# SCH_orange_pi_zero_2022-04-15.net
KiCad netlist of a schematic drawn in EasyEDA
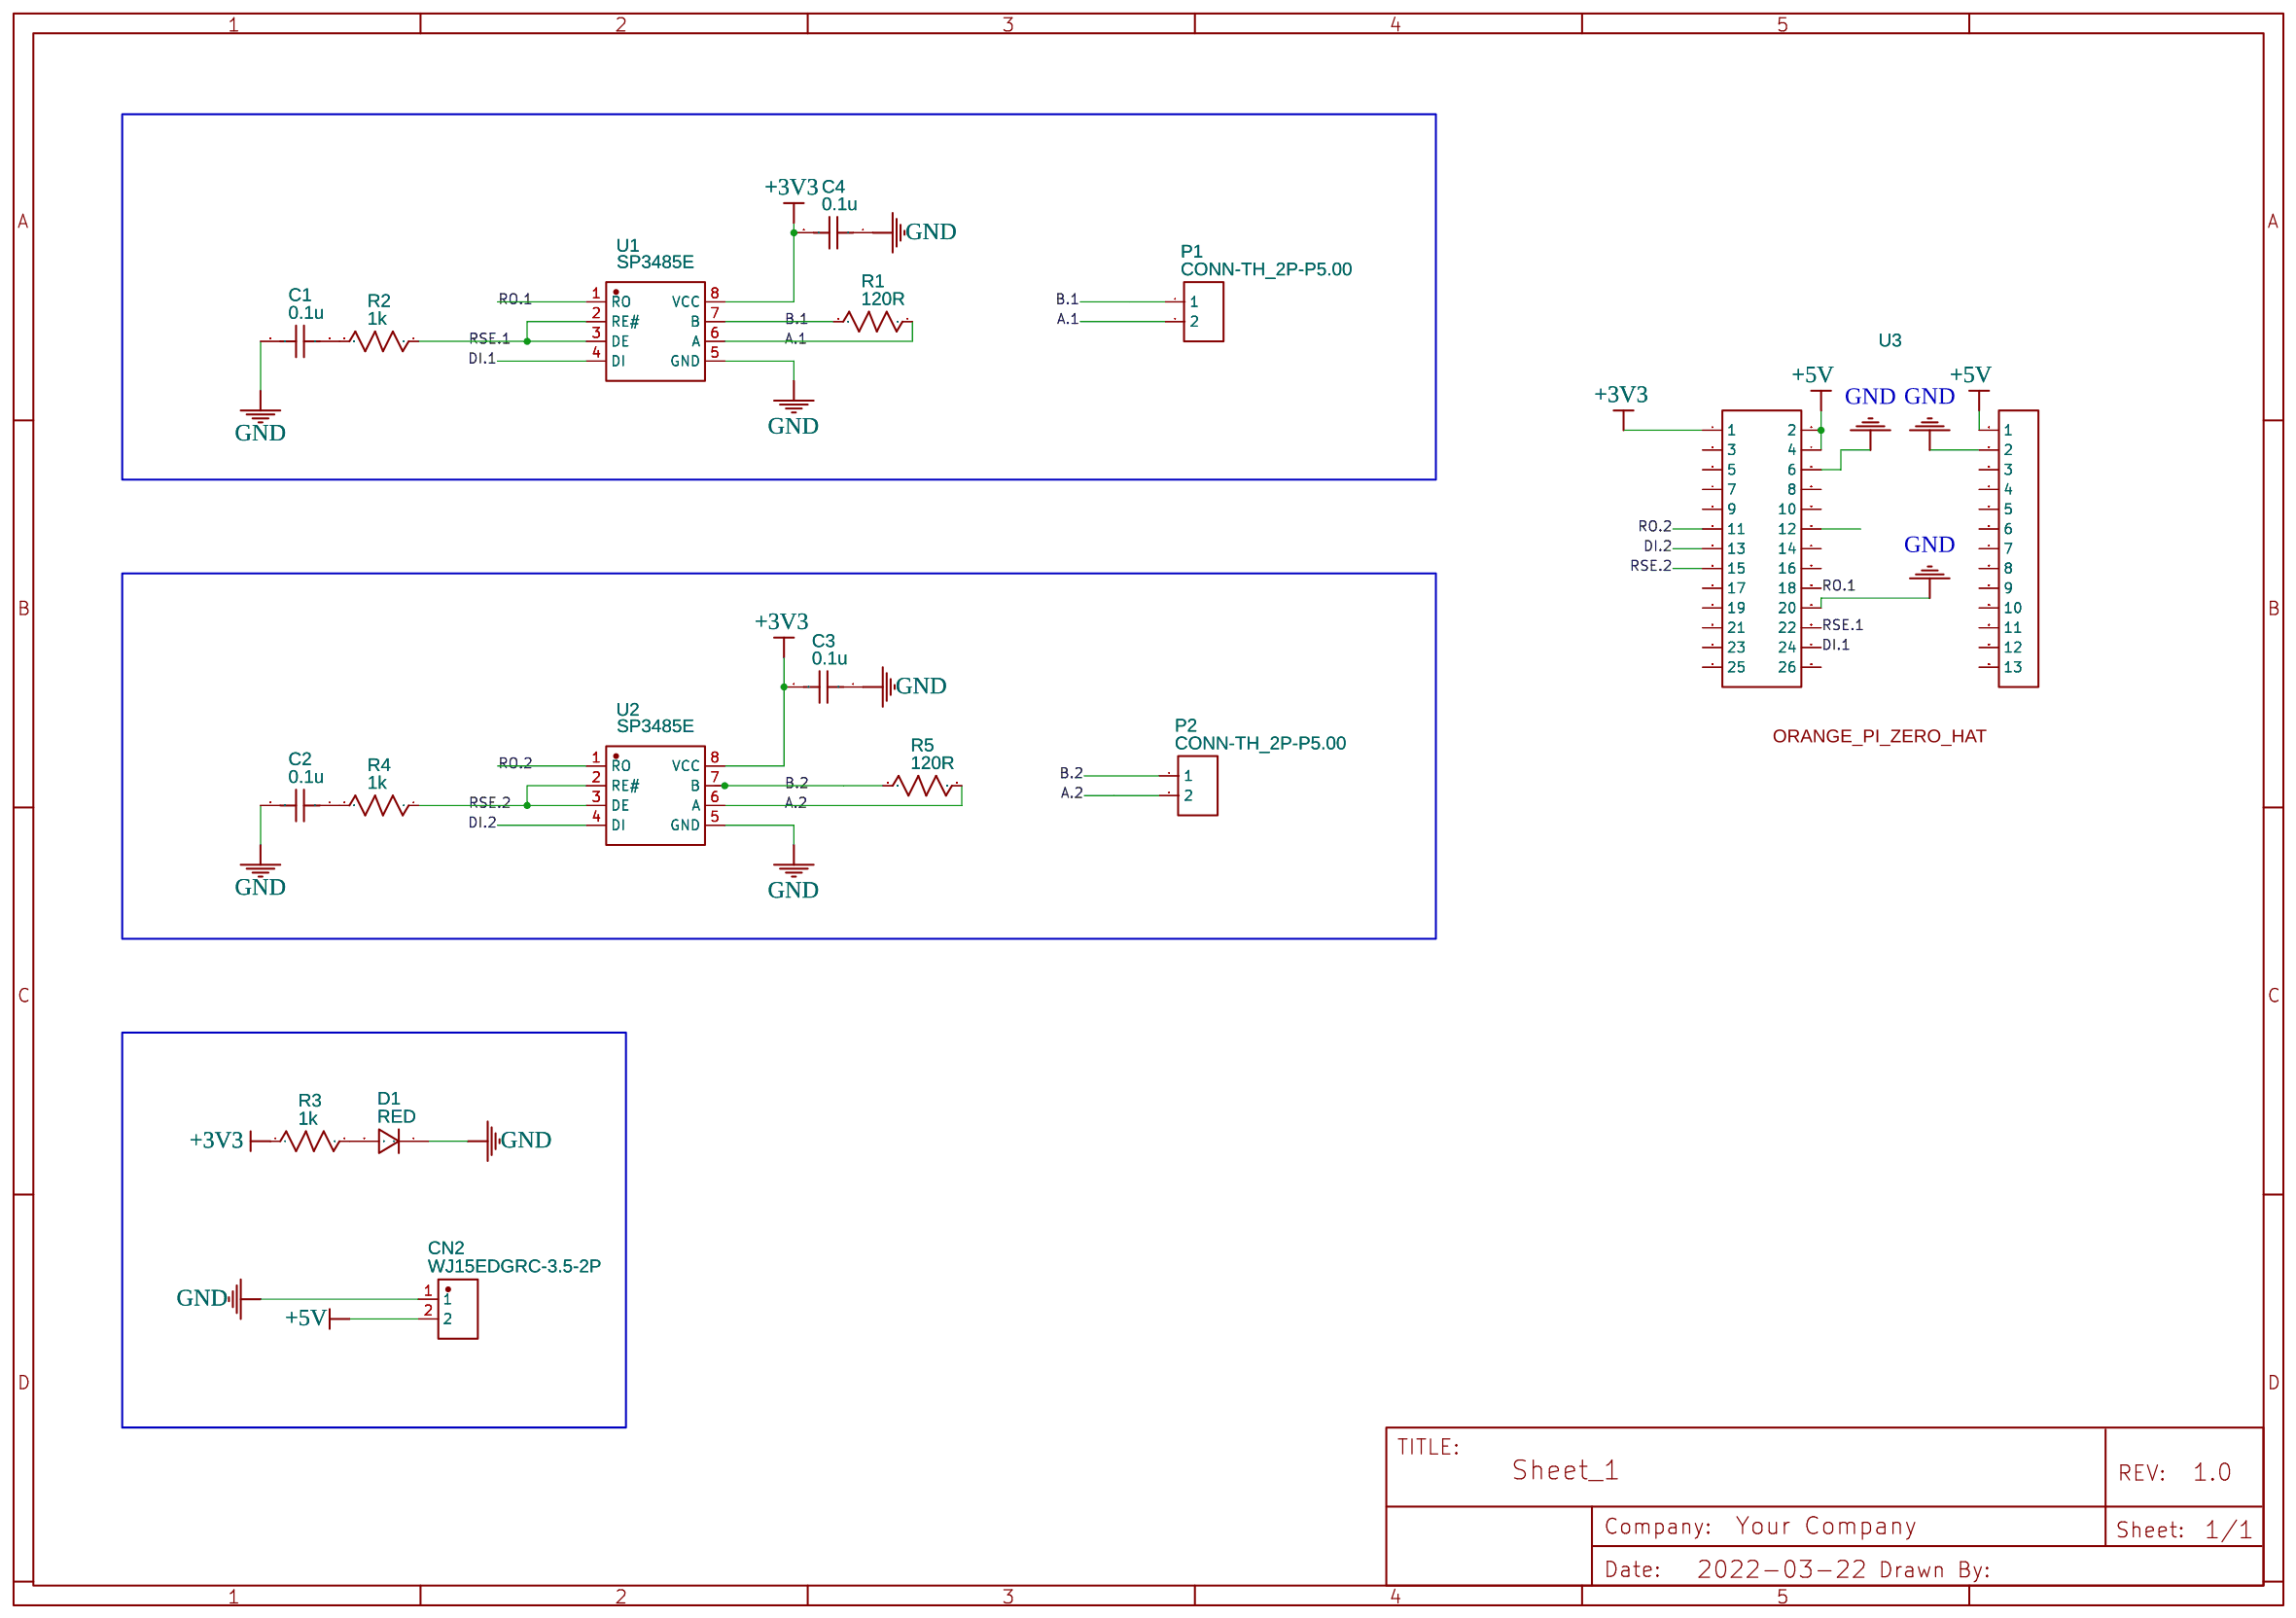
[diagram p0: schematic sheet]

(export (version "E")
  (design (tool "Eeschema 10.0.6"))
  (components
    (comp (ref "C1") (value "0.1u") (libsource (lib "") (part "C_0603_US")))
    (comp (ref "C2") (value "0.1u") (libsource (lib "") (part "C_0603_US")))
    (comp (ref "C3") (value "0.1u") (libsource (lib "") (part "C_0603_US")))
    (comp (ref "C4") (value "0.1u") (libsource (lib "") (part "C_0603_US")))
    (comp (ref "CN2")
      (value "WJ15EDGRC-3.5-2P")
      (fields (field (name "BOM_Supplier Part") "C2924837"))
      (libsource (lib "") (part "WJ15EDGRC-3.5-2P"))
    )
    (comp (ref "D1")
      (value "RED")
      (fields (field (name "BOM_Manufacturer Part") "1N4007W") (field (name "BOM_Supplier Part") "C328592"))
      (libsource (lib "") (part "1N4007W"))
    )
    (comp (ref "P1") (value "CONN-TH_2P-P5.00") (libsource (lib "") (part "CONN-TH_2P-P5.00")))
    (comp (ref "P2") (value "CONN-TH_2P-P5.00") (libsource (lib "") (part "CONN-TH_2P-P5.00")))
    (comp (ref "R1") (value "120R") (libsource (lib "") (part "R_0603_US")))
    (comp (ref "R2") (value "1k") (libsource (lib "") (part "R_0603_US")))
    (comp (ref "R3") (value "1k") (libsource (lib "") (part "R_0603_US_1")))
    (comp (ref "R4") (value "1k") (libsource (lib "") (part "R_0603_US")))
    (comp (ref "R5") (value "120R") (libsource (lib "") (part "R_0603_US")))
    (comp (ref "U1")
      (value "SP3485E")
      (fields
        (field (name "BOM_Manufacturer Part") "SP3485EN-L/TR")
        (field (name "BOM_Supplier Part") "C8963")
      )
      (libsource (lib "") (part "SP3485EN-L/TR"))
    )
    (comp (ref "U2")
      (value "SP3485E")
      (fields
        (field (name "BOM_Manufacturer Part") "SP3485EN-L/TR")
        (field (name "BOM_Supplier Part") "C8963")
      )
      (libsource (lib "") (part "SP3485EN-L/TR"))
    )
    (comp (ref "U3") (value "HDR-F-2.54_2x13") (libsource (lib "") (part "HDR-F-2.54_2x13")))
  )
  (nets
    (net (code "1") (name "+3V3") (class "Default")
      (node (ref "C3") (pin "2") (pinfunction "2_2") (pintype "unspecified"))
      (node (ref "C4") (pin "2") (pinfunction "2_2") (pintype "unspecified"))
      (node (ref "R3") (pin "1") (pinfunction "1_1") (pintype "unspecified"))
      (node (ref "U1") (pin "8") (pinfunction "VCC_8") (pintype "unspecified"))
      (node (ref "U2") (pin "8") (pinfunction "VCC_8") (pintype "unspecified"))
      (node (ref "U3") (pin "1") (pinfunction "1_1") (pintype "passive"))
    )
    (net (code "2") (name "+5V") (class "Default")
      (node (ref "CN2") (pin "2") (pinfunction "2_2") (pintype "unspecified"))
      (node (ref "U3") (pin "2") (pinfunction "2_2") (pintype "passive"))
      (node (ref "U3") (pin "4") (pinfunction "4_4") (pintype "passive"))
      (node (ref "U3") (pin "e1") (pinfunction "1_e1") (pintype "unspecified"))
    )
    (net (code "3") (name "/A.1") (class "Default")
      (node (ref "P1") (pin "2") (pinfunction "2_2") (pintype "unspecified"))
      (node (ref "R1") (pin "1") (pinfunction "1_1") (pintype "unspecified"))
      (node (ref "U1") (pin "6") (pinfunction "A_6") (pintype "unspecified"))
    )
    (net (code "4") (name "/A.2") (class "Default")
      (node (ref "P2") (pin "2") (pinfunction "2_2") (pintype "unspecified"))
      (node (ref "R5") (pin "1") (pinfunction "1_1") (pintype "unspecified"))
      (node (ref "U2") (pin "6") (pinfunction "A_6") (pintype "unspecified"))
    )
    (net (code "5") (name "/B.1") (class "Default")
      (node (ref "P1") (pin "1") (pinfunction "1_1") (pintype "unspecified"))
      (node (ref "R1") (pin "2") (pinfunction "2_2") (pintype "unspecified"))
      (node (ref "U1") (pin "7") (pinfunction "B_7") (pintype "unspecified"))
    )
    (net (code "6") (name "/B.2") (class "Default")
      (node (ref "P2") (pin "1") (pinfunction "1_1") (pintype "unspecified"))
      (node (ref "R5") (pin "2") (pinfunction "2_2") (pintype "unspecified"))
      (node (ref "U2") (pin "7") (pinfunction "B_7") (pintype "unspecified"))
    )
    (net (code "7") (name "/DI.1") (class "Default")
      (node (ref "U1") (pin "4") (pinfunction "DI_4") (pintype "unspecified"))
      (node (ref "U3") (pin "24") (pinfunction "24_24") (pintype "input"))
    )
    (net (code "8") (name "/DI.2") (class "Default")
      (node (ref "U2") (pin "4") (pinfunction "DI_4") (pintype "unspecified"))
      (node (ref "U3") (pin "13") (pinfunction "13_13") (pintype "input"))
    )
    (net (code "9") (name "/RO.1") (class "Default")
      (node (ref "U1") (pin "1") (pinfunction "RO_1") (pintype "unspecified"))
      (node (ref "U3") (pin "18") (pinfunction "18_18") (pintype "input"))
    )
    (net (code "10") (name "/RO.2") (class "Default")
      (node (ref "U2") (pin "1") (pinfunction "RO_1") (pintype "unspecified"))
      (node (ref "U3") (pin "11") (pinfunction "11_11") (pintype "input"))
    )
    (net (code "11") (name "/RSE.1") (class "Default")
      (node (ref "R2") (pin "1") (pinfunction "1_1") (pintype "unspecified"))
      (node (ref "U1") (pin "2") (pinfunction "RE#_2") (pintype "unspecified"))
      (node (ref "U1") (pin "3") (pinfunction "DE_3") (pintype "unspecified"))
      (node (ref "U3") (pin "22") (pinfunction "22_22") (pintype "input"))
    )
    (net (code "12") (name "/RSE.2") (class "Default")
      (node (ref "R4") (pin "1") (pinfunction "1_1") (pintype "unspecified"))
      (node (ref "U2") (pin "2") (pinfunction "RE#_2") (pintype "unspecified"))
      (node (ref "U2") (pin "3") (pinfunction "DE_3") (pintype "unspecified"))
      (node (ref "U3") (pin "15") (pinfunction "15_15") (pintype "input"))
    )
    (net (code "13") (name "GND") (class "Default")
      (node (ref "C1") (pin "2") (pinfunction "2_2") (pintype "unspecified"))
      (node (ref "C2") (pin "2") (pinfunction "2_2") (pintype "unspecified"))
      (node (ref "C3") (pin "1") (pinfunction "1_1") (pintype "unspecified"))
      (node (ref "C4") (pin "1") (pinfunction "1_1") (pintype "unspecified"))
      (node (ref "CN2") (pin "1") (pinfunction "1_1") (pintype "unspecified"))
      (node (ref "D1") (pin "1") (pinfunction "1_1") (pintype "unspecified"))
      (node (ref "U1") (pin "5") (pinfunction "GND_5") (pintype "unspecified"))
      (node (ref "U2") (pin "5") (pinfunction "GND_5") (pintype "unspecified"))
      (node (ref "U3") (pin "20") (pinfunction "20_20") (pintype "input"))
      (node (ref "U3") (pin "6") (pinfunction "6_6") (pintype "input"))
      (node (ref "U3") (pin "e2") (pinfunction "2_e2") (pintype "unspecified"))
    )
    (net (code "14") (name "Net-(C1-Pad1)") (class "Default")
      (node (ref "C1") (pin "1") (pinfunction "1_1") (pintype "unspecified"))
      (node (ref "R2") (pin "2") (pinfunction "2_2") (pintype "unspecified"))
    )
    (net (code "15") (name "Net-(C2-Pad1)") (class "Default")
      (node (ref "C2") (pin "1") (pinfunction "1_1") (pintype "unspecified"))
      (node (ref "R4") (pin "2") (pinfunction "2_2") (pintype "unspecified"))
    )
    (net (code "16") (name "Net-(D1-Pad2)") (class "Default")
      (node (ref "D1") (pin "2") (pinfunction "2_2") (pintype "unspecified"))
      (node (ref "R3") (pin "2") (pinfunction "2_2") (pintype "unspecified"))
    )
    (net (code "17") (name "unconnected-(U3-3-Pade3)") (class "Default")
      (node (ref "U3") (pin "e3") (pinfunction "3_e3") (pintype "unspecified"))
    )
    (net (code "18") (name "unconnected-(U3-4-Pade4)") (class "Default")
      (node (ref "U3") (pin "e4") (pinfunction "4_e4") (pintype "unspecified"))
    )
    (net (code "19") (name "unconnected-(U3-5-Pade5)") (class "Default")
      (node (ref "U3") (pin "e5") (pinfunction "5_e5") (pintype "unspecified"))
    )
    (net (code "20") (name "unconnected-(U3-6-Pade6)") (class "Default")
      (node (ref "U3") (pin "e6") (pinfunction "6_e6") (pintype "unspecified"))
    )
    (net (code "21") (name "unconnected-(U3-7-Pade7)") (class "Default")
      (node (ref "U3") (pin "e7") (pinfunction "7_e7") (pintype "unspecified"))
    )
    (net (code "22") (name "unconnected-(U3-8-Pade8)") (class "Default")
      (node (ref "U3") (pin "e8") (pinfunction "8_e8") (pintype "unspecified"))
    )
    (net (code "23") (name "unconnected-(U3-9-Pade9)") (class "Default")
      (node (ref "U3") (pin "e9") (pinfunction "9_e9") (pintype "unspecified"))
    )
    (net (code "24") (name "unconnected-(U3-10-Pade10)") (class "Default")
      (node (ref "U3") (pin "e10") (pinfunction "10_e10") (pintype "unspecified"))
    )
    (net (code "25") (name "unconnected-(U3-11-Pade11)") (class "Default")
      (node (ref "U3") (pin "e11") (pinfunction "11_e11") (pintype "unspecified"))
    )
    (net (code "26") (name "unconnected-(U3-12-Pade12)") (class "Default")
      (node (ref "U3") (pin "e12") (pinfunction "12_e12") (pintype "unspecified"))
    )
    (net (code "27") (name "unconnected-(U3-13-Pade13)") (class "Default")
      (node (ref "U3") (pin "e13") (pinfunction "13_e13") (pintype "unspecified"))
    )
    (net (code "28") (name "unconnected-(U3-Pad3)") (class "Default")
      (node (ref "U3") (pin "3") (pinfunction "3_3") (pintype "input"))
    )
    (net (code "29") (name "unconnected-(U3-Pad5)") (class "Default")
      (node (ref "U3") (pin "5") (pinfunction "5_5") (pintype "input"))
    )
    (net (code "30") (name "unconnected-(U3-Pad7)") (class "Default")
      (node (ref "U3") (pin "7") (pinfunction "7_7") (pintype "input"))
    )
    (net (code "31") (name "unconnected-(U3-Pad8)") (class "Default")
      (node (ref "U3") (pin "8") (pinfunction "8_8") (pintype "input"))
    )
    (net (code "32") (name "unconnected-(U3-Pad9)") (class "Default")
      (node (ref "U3") (pin "9") (pinfunction "9_9") (pintype "input"))
    )
    (net (code "33") (name "unconnected-(U3-Pad10)") (class "Default")
      (node (ref "U3") (pin "10") (pinfunction "10_10") (pintype "input"))
    )
    (net (code "34") (name "unconnected-(U3-Pad12)") (class "Default")
      (node (ref "U3") (pin "12") (pinfunction "12_12") (pintype "input"))
    )
    (net (code "35") (name "unconnected-(U3-Pad14)") (class "Default")
      (node (ref "U3") (pin "14") (pinfunction "14_14") (pintype "input"))
    )
    (net (code "36") (name "unconnected-(U3-Pad16)") (class "Default")
      (node (ref "U3") (pin "16") (pinfunction "16_16") (pintype "input"))
    )
    (net (code "37") (name "unconnected-(U3-Pad17)") (class "Default")
      (node (ref "U3") (pin "17") (pinfunction "17_17") (pintype "passive"))
    )
    (net (code "38") (name "unconnected-(U3-Pad19)") (class "Default")
      (node (ref "U3") (pin "19") (pinfunction "19_19") (pintype "input"))
    )
    (net (code "39") (name "unconnected-(U3-Pad21)") (class "Default")
      (node (ref "U3") (pin "21") (pinfunction "21_21") (pintype "input"))
    )
    (net (code "40") (name "unconnected-(U3-Pad23)") (class "Default")
      (node (ref "U3") (pin "23") (pinfunction "23_23") (pintype "input"))
    )
    (net (code "41") (name "unconnected-(U3-Pad25)") (class "Default")
      (node (ref "U3") (pin "25") (pinfunction "25_25") (pintype "input"))
    )
    (net (code "42") (name "unconnected-(U3-Pad26)") (class "Default")
      (node (ref "U3") (pin "26") (pinfunction "26_26") (pintype "input"))
    )
  )
)
